# AVCF-Schematics.net
KiCad netlist of a schematic drawn in Altium Designer
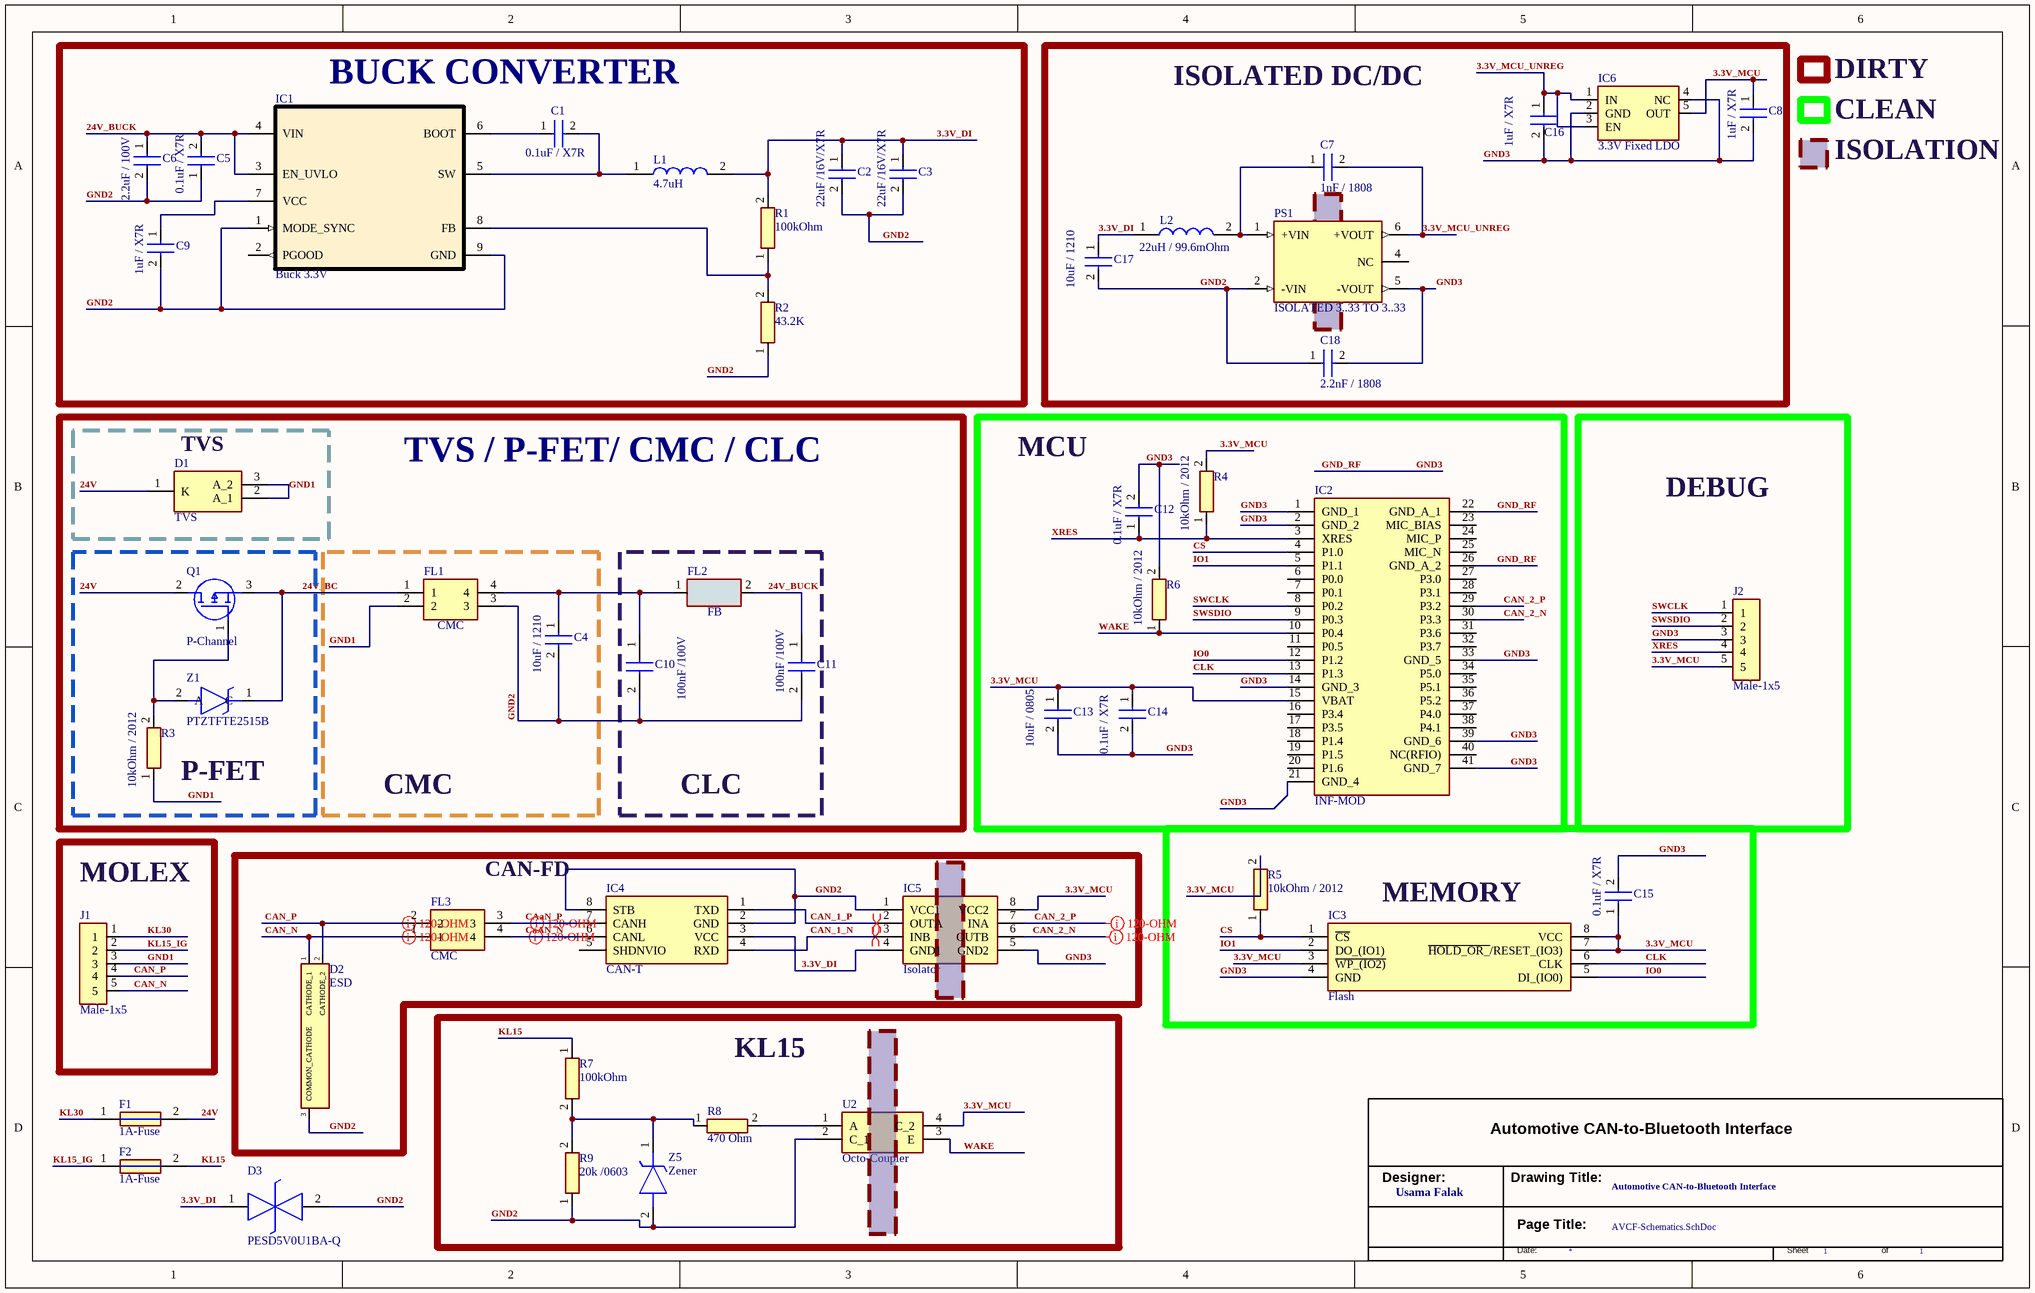
[diagram p0: AVCF-Schematics.SchDoc]

(export (version "E")
  (design (tool "Eeschema 10.0.6"))
  (components
    (comp (ref "*") (value "TitleBlock_MCPG") (libsource (lib "AVCF-SCH_Lib") (part "TitleBlock_MCPG")))
    (comp (ref "C1")
      (value "0.1uF / X7R")
      (footprint "MAJx16")
      (description "Capacitor")
      (fields (field (name "MANUFACTURER_PART_NUMBER") "MAJCU168BB7104KTEA01"))
      (libsource (lib "AVCF-SCH_Lib") (part "MAJCU168BB7104KTEA01"))
    )
    (comp (ref "C2")
      (value "22uF /16V/X7R")
      (footprint "AVCF-PCB_Lib:CAPC3225X280N")
      (description "Capacitor")
      (fields
        (field (name "MANUFACTURER_PART_NUMBER") "CGA6P1X7R1C226M250AC")
        (field (name "MOUSER PART NUMBER") "810-CGA6P1X7R1C226M")
      )
      (libsource (lib "AVCF-SCH_Lib") (part "CGA6P1X7R1C226M250AC"))
    )
    (comp (ref "C3")
      (value "22uF /16V/X7R")
      (footprint "AVCF-PCB_Lib:CAPC3225X280N")
      (description "Capacitor")
      (fields
        (field (name "MANUFACTURER_PART_NUMBER") "CGA6P1X7R1C226M250AC")
        (field (name "MOUSER PART NUMBER") "810-CGA6P1X7R1C226M")
      )
      (libsource (lib "AVCF-SCH_Lib") (part "CGA6P1X7R1C226M250AC"))
    )
    (comp (ref "C4")
      (value "10uF / 1210")
      (footprint "AVCF-PCB_Lib:CAPC3225X280N")
      (description "Capacitor")
      (fields (field (name "MANUFACTURER_PART_NUMBER") "CGA6P1X7R2A106K250AC"))
      (libsource (lib "AVCF-SCH_Lib") (part "CGA6P1X7R2A106K250AC"))
    )
    (comp (ref "C5")
      (value "0.1uF / X7R")
      (footprint "MAJx16")
      (description "Capacitor")
      (fields (field (name "MANUFACTURER_PART_NUMBER") "MAJCU168BB7104KTEA01"))
      (libsource (lib "AVCF-SCH_Lib") (part "MAJCU168BB7104KTEA01"))
    )
    (comp (ref "C6")
      (value "2.2uF / 100V")
      (footprint "AVCF-PCB_Lib:CGA4J2NP01H223J125AA")
      (description "Capacitor")
      (fields
        (field (name "MANUFACTURER_PART_NUMBER") "CGA4J1X7R2A225K125AC")
        (field (name "MOUSER PART NUMBER") "810-CGA4J7R2A225K125")
      )
      (libsource (lib "AVCF-SCH_Lib") (part "CGA4J1X7R2A225K125AC"))
    )
    (comp (ref "C7")
      (value "1nF / 1808")
      (footprint "AVCF-PCB_Lib:C1808")
      (description "Capacitor")
      (fields
        (field (name "MANUFACTURER_PART_NUMBER") "C1808C102JBGACAUTO")
        (field (name "MOUSER PART NUMBER") "80-C1808C102JBGAUTO")
      )
      (libsource (lib "AVCF-SCH_Lib") (part "C1808C102JBGACAUTO"))
    )
    (comp (ref "C8")
      (value "1uF / X7R")
      (footprint "CAPC1608X100N")
      (description "Capacitor")
      (fields
        (field (name "MANUFACTURER_PART_NUMBER") "CL10B105KB9VPNC")
        (field (name "MOUSER PART NUMBER") "187-CL10B105KB9VPNC")
      )
      (libsource (lib "AVCF-SCH_Lib") (part "CL10B105KB9VPNC"))
    )
    (comp (ref "C9")
      (value "1uF / X7R")
      (footprint "CAPC1608X100N")
      (description "Capacitor")
      (fields
        (field (name "MANUFACTURER_PART_NUMBER") "CL10B105KB9VPNC")
        (field (name "MOUSER PART NUMBER") "187-CL10B105KB9VPNC")
      )
      (libsource (lib "AVCF-SCH_Lib") (part "CL10B105KB9VPNC"))
    )
    (comp (ref "C10")
      (value "100nF /100V")
      (footprint "AVCF-PCB_Lib:CAPC1608X87N")
      (description "Multilayer Ceramic Capacitors MLCC - SMD/SMT 100V 100000pF 5% X7R 1608 AEC-Q200")
      (fields
        (field (name "MANUFACTURER_PART_NUMBER") "C0603C104J1RACAUTO7411")
        (field (name "MOUSER PART NUMBER") "80-C0603C104J1RAUTO7")
      )
      (libsource (lib "AVCF-SCH_Lib") (part "C0603C104J1RACAUTO7411"))
    )
    (comp (ref "C11")
      (value "100nF /100V")
      (footprint "AVCF-PCB_Lib:CAPC1608X87N")
      (description "Multilayer Ceramic Capacitors MLCC - SMD/SMT 100V 100000pF 5% X7R 1608 AEC-Q200")
      (fields
        (field (name "MANUFACTURER_PART_NUMBER") "C0603C104J1RACAUTO7411")
        (field (name "MOUSER PART NUMBER") "80-C0603C104J1RAUTO7")
      )
      (libsource (lib "AVCF-SCH_Lib") (part "C0603C104J1RACAUTO7411"))
    )
    (comp (ref "C12")
      (value "0.1uF / X7R")
      (footprint "MAJx16")
      (description "Capacitor")
      (fields (field (name "MANUFACTURER_PART_NUMBER") "MAJCU168BB7104KTEA01"))
      (libsource (lib "AVCF-SCH_Lib") (part "MAJCU168BB7104KTEA01"))
    )
    (comp (ref "C13")
      (value "10uF / 0805")
      (footprint "AVCF-PCB_Lib:CGA4J2NP01H223J125AA")
      (description "Capacitor")
      (fields
        (field (name "MANUFACTURER_PART_NUMBER") "CGA4J1X7S1C106M125AE")
        (field (name "MOUSER PART NUMBER") "810-CGA4J1X7S1C106MA")
      )
      (libsource (lib "AVCF-SCH_Lib") (part "CGA4J1X7S1C106M125AE"))
    )
    (comp (ref "C14")
      (value "0.1uF / X7R")
      (footprint "MAJx16")
      (description "Capacitor")
      (fields (field (name "MANUFACTURER_PART_NUMBER") "MAJCU168BB7104KTEA01"))
      (libsource (lib "AVCF-SCH_Lib") (part "MAJCU168BB7104KTEA01"))
    )
    (comp (ref "C15")
      (value "0.1uF / X7R")
      (footprint "MAJx16")
      (description "Capacitor")
      (fields (field (name "MANUFACTURER_PART_NUMBER") "MAJCU168BB7104KTEA01"))
      (libsource (lib "AVCF-SCH_Lib") (part "MAJCU168BB7104KTEA01"))
    )
    (comp (ref "C16")
      (value "1uF / X7R")
      (footprint "CAPC1608X100N")
      (description "Capacitor")
      (fields
        (field (name "MANUFACTURER_PART_NUMBER") "CL10B105KB9VPNC")
        (field (name "MOUSER PART NUMBER") "187-CL10B105KB9VPNC")
      )
      (libsource (lib "AVCF-SCH_Lib") (part "CL10B105KB9VPNC"))
    )
    (comp (ref "C17")
      (value "10uF / 1210")
      (footprint "AVCF-PCB_Lib:CAPC3225X280N")
      (description "Capacitor")
      (fields (field (name "MANUFACTURER_PART_NUMBER") "CGA6P1X7R2A106K250AC"))
      (libsource (lib "AVCF-SCH_Lib") (part "CGA6P1X7R2A106K250AC"))
    )
    (comp (ref "C18")
      (value "2.2nF / 1808")
      (footprint "AVCF-PCB_Lib:C1808")
      (description "Capacitor")
      (fields (field (name "MANUFACTURER_PART_NUMBER") "C1808C222FDGACAUTO"))
      (libsource (lib "AVCF-SCH_Lib") (part "C1808C222FDGACAUTO"))
    )
    (comp (ref "D1")
      (value "TVS")
      (footprint "AVCF-PCB_Lib:SLD8S36A")
      (description "TVS Diode (Uni-directional)")
      (fields
        (field (name "MANUFACTURER_PART_NUMBER") "SLD8S36A")
        (field (name "MOUSER PART NUMBER") "576-SLD8S36A")
      )
      (libsource (lib "AVCF-SCH_Lib") (part "SLD8S36A"))
    )
    (comp (ref "D2")
      (value "ESD")
      (footprint "SOT95P230X110-3N")
      (description "Diode ESD (Bi-directional)")
      (fields
        (field (name "MANUFACTURER_PART_NUMBER") "PESD2CAN,215")
        (field (name "MOUSER PART NUMBER") "771-PESD2CAN-T/R")
      )
      (libsource (lib "AVCF-SCH_Lib") (part "PESD2CAN,215"))
    )
    (comp (ref "D3")
      (value "PESD5V0U1BA‑Q")
      (footprint "AVCF-PCB_Lib:PESD5V0U1BA115")
      (description "Diode ESD (Bi-directional)")
      (fields
        (field (name "MANUFACTURER_PART_NUMBER") "PESD5V0U1BA-Q")
        (field (name "MOUSER PART NUMBER") "771-PESD5V0U1BA115")
      )
      (libsource (lib "AVCF-SCH_Lib") (part "PESD5V0U1BA"))
    )
    (comp (ref "F1")
      (value "1A-Fuse")
      (footprint "AVCF-PCB_Lib:FUSC6127X294N")
      (description "Fuse")
      (fields
        (field (name "MANUFACTURER_PART_NUMBER") "0451001.MRSN")
        (field (name "MOUSER PART NUMBER") "576-0451001.MRSN")
      )
      (libsource (lib "AVCF-SCH_Lib") (part "0451001.MRSN"))
    )
    (comp (ref "F2")
      (value "1A-Fuse")
      (footprint "AVCF-PCB_Lib:FUSC6127X294N")
      (description "Fuse")
      (fields
        (field (name "MANUFACTURER_PART_NUMBER") "0451001.MRSN")
        (field (name "MOUSER PART NUMBER") "576-0451001.MRSN")
      )
      (libsource (lib "AVCF-SCH_Lib") (part "0451001.MRSN"))
    )
    (comp (ref "FL1")
      (value "CMC")
      (footprint "ACT45B1012PTL003")
      (description "Filter")
      (fields
        (field (name "MANUFACTURER_PART_NUMBER") "ACT45B-510-2P-TL003")
        (field (name "MOUSER PART NUMBER") "810-ACT45B5102PTL003")
      )
      (libsource (lib "") (part "ACT45B-510-2P-TL003_1"))
    )
    (comp (ref "FL2")
      (value "FB")
      (footprint "BLM31KN102BH1L")
      (description "Filter")
      (fields
        (field (name "MANUFACTURER_PART_NUMBER") "BLM31KN601SZ1L")
        (field (name "MOUSER PART NUMBER") "81-BLM31KN601SZ1L")
      )
      (libsource (lib "AVCF-SCH_Lib") (part "BLM31KN601SZ1L"))
    )
    (comp (ref "FL3")
      (value "CMC")
      (footprint "ACT45B1012PTL003")
      (description "Filter")
      (fields
        (field (name "MANUFACTURER_PART_NUMBER") "ACT45B-510-2P-TL003")
        (field (name "MOUSER PART NUMBER") "810-ACT45B5102PTL003")
      )
      (libsource (lib "AVCF-SCH_Lib") (part "ACT45B-510-2P-TL003"))
    )
    (comp (ref "IC1")
      (value "Buck 3.3V")
      (footprint "RPE0009A")
      (fields
        (field (name "MANUFACTURER_PART_NUMBER") "LMR36506MSC3RPERQ1")
        (field (name "COPYRIGHT") "Copyright (C) 2025 Ultra Librarian. All rights reserved.")
      )
      (libsource (lib "AVCF-SCH_Lib") (part "LMR36506MSC3RPERQ1"))
    )
    (comp (ref "IC2")
      (value "INF-MOD")
      (footprint "CYW20829B0P4TAI100XUMA1")
      (description "Integrated Circuit")
      (fields
        (field (name "MANUFACTURER_PART_NUMBER") "CYW20829B0P4TAI100XUMA1")
        (field (name "MOUSER PART NUMBER") "726-CYW20829B0P4TAI1")
      )
      (libsource (lib "AVCF-SCH_Lib") (part "CYW20829B0P4TAI100XUMA1"))
    )
    (comp (ref "IC3")
      (value "Flash")
      (footprint "AVCF-PCB_Lib:SOIC127P790X216-8N")
      (description "Integrated Circuit")
      (fields
        (field (name "MANUFACTURER_PART_NUMBER") "W25Q128JVSIM")
        (field (name "MOUSER PART NUMBER") "454-W25Q128JVSIM")
      )
      (libsource (lib "AVCF-SCH_Lib") (part "W25Q128JVSIM"))
    )
    (comp (ref "IC4")
      (value "CAN-T")
      (footprint "AVCF-PCB_Lib:SOIC127P600X175-8N")
      (description "Integrated Circuit")
      (fields
        (field (name "MANUFACTURER_PART_NUMBER") "TCAN3403DRQ1")
        (field (name "MOUSER PART NUMBER") "595-TCAN3403DRQ1")
      )
      (libsource (lib "AVCF-SCH_Lib") (part "TCAN3403DRQ1"))
    )
    (comp (ref "IC5")
      (value "Isolator")
      (footprint "SOIC127P600X175-8N")
      (description "Integrated Circuit")
      (fields
        (field (name "MANUFACTURER_PART_NUMBER") "ISO7721D")
        (field (name "MOUSER PART NUMBER") "595-ISO7721D")
      )
      (libsource (lib "AVCF-SCH_Lib") (part "ISO7721D"))
    )
    (comp (ref "IC6")
      (value "3.3V Fixed LDO")
      (footprint "AVCF-PCB_Lib:SOT95P280X145-5N")
      (description "Linear Voltage Regulator IC Positive Fixed 1 Output 300mA SOT-23-5")
      (fields
        (field (name "MANUFACTURER_PART_NUMBER") "TLV70233PDBVT")
        (field (name "MOUSER PART NUMBER") "595-TLV70233PDBVT")
      )
      (libsource (lib "AVCF-SCH_Lib") (part "TLV70233PDBVT"))
    )
    (comp (ref "J1")
      (value "Male-1x5")
      (footprint "43650-05(12,13,14)")
      (description "Connector")
      (fields
        (field (name "MANUFACTURER_PART_NUMBER") "43650-0513")
        (field (name "MOUSER PART NUMBER") "538-43650-0513")
      )
      (libsource (lib "") (part "43650-0513_1"))
    )
    (comp (ref "J2")
      (value "Male-1x5")
      (footprint "43650-05(12,13,14)")
      (description "Connector")
      (fields
        (field (name "MANUFACTURER_PART_NUMBER") "43650-0513")
        (field (name "MOUSER PART NUMBER") "538-43650-0513")
      )
      (libsource (lib "AVCF-SCH_Lib") (part "43650-0513"))
    )
    (comp (ref "L1")
      (value "4.7uH")
      (footprint "AVCF-PCB_Lib:MSS6132T472MLC")
      (description "Inductor")
      (fields
        (field (name "MANUFACTURER_PART_NUMBER") "MSS6132T-472MLC")
        (field (name "MOUSER PART NUMBER") "994-MSS6132T-472MLC")
      )
      (libsource (lib "AVCF-SCH_Lib") (part "MSS6132T-472MLC"))
    )
    (comp (ref "L2")
      (value "22uH / 99.6mOhm")
      (footprint "XAL5030")
      (description "Inductor")
      (fields
        (field (name "MANUFACTURER_PART_NUMBER") "XAL5050-223MEC")
        (field (name "MOUSER PART NUMBER") "994-XAL5050-223MEC")
      )
      (libsource (lib "AVCF-SCH_Lib") (part "XAL5050-223MEC"))
    )
    (comp (ref "PS1")
      (value "ISOLATED 3..33 TO 3..33")
      (footprint "CONV_RB-3.33.3S")
      (description "1W DC/DC-Converter 'ECONOLINE' SIP7 1kV unreg")
      (fields (field (name "MF") "Recom Power") (field (name "MP") "RB-3.33.3S"))
      (libsource (lib "AVCF-SCH_Lib") (part "RB-3.33.3S"))
    )
    (comp (ref "Q1")
      (value "P-Channel")
      (footprint "FQD20N06TM")
      (description "MOSFET (P-Channel)")
      (fields
        (field (name "MANUFACTURER_PART_NUMBER") "FQD8P10TM-F085")
        (field (name "MOUSER PART NUMBER") "512-FQD8P10TM_F085")
      )
      (libsource (lib "AVCF-SCH_Lib") (part "FQD8P10TM-F085"))
    )
    (comp (ref "R1")
      (value "100kOhm")
      (footprint "AVCF-PCB_Lib:RCS0805_E3")
      (description "Resistor")
      (fields
        (field (name "MANUFACTURER_PART_NUMBER") "RCS0805100KFKEA")
        (field (name "MOUSER PART NUMBER") "71-RCS0805100KFKEA")
      )
      (libsource (lib "") (part "RCS0805100KFKEA_1"))
    )
    (comp (ref "R2")
      (value "43.2K")
      (footprint "AVCF-PCB_Lib:ERJP03_PA3_(0603)")
      (description "Resistor")
      (fields
        (field (name "MANUFACTURER_PART_NUMBER") "ERJ-PA3D4322V")
        (field (name "MOUSER PART NUMBER") "667-ERJ-PA3D4322V")
      )
      (libsource (lib "AVCF-SCH_Lib") (part "ERJ-PA3D4322V"))
    )
    (comp (ref "R3")
      (value "10kOhm / 2012")
      (footprint "RESC2012X60N")
      (description "Resistor")
      (fields
        (field (name "MANUFACTURER_PART_NUMBER") "RT0805FRE1010KL")
        (field (name "MOUSER PART NUMBER") "603-RT0805FRE1010KL")
      )
      (libsource (lib "AVCF-SCH_Lib") (part "RT0805FRE1010KL"))
    )
    (comp (ref "R4")
      (value "10kOhm / 2012")
      (footprint "RESC2012X60N")
      (description "Resistor")
      (fields
        (field (name "MANUFACTURER_PART_NUMBER") "RT0805FRE1010KL")
        (field (name "MOUSER PART NUMBER") "603-RT0805FRE1010KL")
      )
      (libsource (lib "AVCF-SCH_Lib") (part "RT0805FRE1010KL"))
    )
    (comp (ref "R5")
      (value "10kOhm / 2012")
      (footprint "RESC2012X60N")
      (description "Resistor")
      (fields
        (field (name "MANUFACTURER_PART_NUMBER") "RT0805FRE1010KL")
        (field (name "MOUSER PART NUMBER") "603-RT0805FRE1010KL")
      )
      (libsource (lib "AVCF-SCH_Lib") (part "RT0805FRE1010KL"))
    )
    (comp (ref "R6")
      (value "10kOhm / 2012")
      (footprint "RESC2012X60N")
      (description "Resistor")
      (fields
        (field (name "MANUFACTURER_PART_NUMBER") "RT0805FRE1010KL")
        (field (name "MOUSER PART NUMBER") "603-RT0805FRE1010KL")
      )
      (libsource (lib "AVCF-SCH_Lib") (part "RT0805FRE1010KL"))
    )
    (comp (ref "R7")
      (value "100kOhm")
      (footprint "AVCF-PCB_Lib:RCS0805_E3")
      (description "Resistor")
      (fields
        (field (name "MANUFACTURER_PART_NUMBER") "RCS0805100KFKEA")
        (field (name "MOUSER PART NUMBER") "71-RCS0805100KFKEA")
      )
      (libsource (lib "AVCF-SCH_Lib") (part "RCS0805100KFKEA"))
    )
    (comp (ref "R8")
      (value "470 Ohm")
      (footprint "AVCF-PCB_Lib:RESC2012X50N")
      (description "Resistor")
      (fields
        (field (name "MANUFACTURER_PART_NUMBER") "RCS0805470RJNEA")
        (field (name "MOUSER PART NUMBER") "71-RCS0805470RJNEA")
      )
      (libsource (lib "AVCF-SCH_Lib") (part "RCS0805470RJNEA"))
    )
    (comp (ref "R9")
      (value "20k /0603")
      (footprint "AVCF-PCB_Lib:RESC1608X55N")
      (description "Resistor")
      (fields
        (field (name "MANUFACTURER_PART_NUMBER") "CRCW060320K0FKEAHP")
        (field (name "MOUSER PART NUMBER") "71-CRCW060320K0FKEAH")
      )
      (libsource (lib "AVCF-SCH_Lib") (part "CRCW060320K0FKEAHP"))
    )
    (comp (ref "U2")
      (value "Octo-Coupler")
      (footprint "AVCF-PCB_Lib:SOP254P695X242-4N")
      (description "Undefined or Miscellaneous")
      (fields
        (field (name "MANUFACTURER_PART_NUMBER") "VOMA617A-3X001T")
        (field (name "MOUSER PART NUMBER") "78-VOMA617A-3X001T")
      )
      (libsource (lib "AVCF-SCH_Lib") (part "VOMA617A-3X001T"))
    )
    (comp (ref "Z1")
      (value "PTZTFTE2515B")
      (footprint "PTZTFTE2515B")
      (description "Zener Diode")
      (fields (field (name "MOUSER PART NUMBER") "755-PTZTFTE2515B"))
      (libsource (lib "AVCF-SCH_Lib") (part "PTZTFTE2515B"))
    )
    (comp (ref "Z5")
      (value "Zener")
      (footprint "AVCF-PCB_Lib:SOD3716X145N")
      (description "Zener Diode")
      (fields
        (field (name "MANUFACTURER_PART_NUMBER") "BZT52C5V1-7-F")
        (field (name "MOUSER PART NUMBER") "621-BZT52C5V1-F")
      )
      (libsource (lib "AVCF-SCH_Lib") (part "BZT52C5V1-7-F"))
    )
  )
  (nets
    (net (code "1") (name "/3.3V_DI") (class "Default")
      (node (ref "C17") (pin "1") (pinfunction "1_1") (pintype "passive"))
      (node (ref "C2") (pin "1") (pinfunction "1_1") (pintype "passive"))
      (node (ref "C3") (pin "1") (pinfunction "1_1") (pintype "passive"))
      (node (ref "D3") (pin "1") (pinfunction "K1_1") (pintype "passive"))
      (node (ref "IC4") (pin "3") (pinfunction "VCC_3") (pintype "passive"))
      (node (ref "IC5") (pin "4") (pinfunction "GND1_4") (pintype "passive"))
      (node (ref "L1") (pin "2") (pinfunction "2_2") (pintype "passive"))
      (node (ref "L2") (pin "1") (pinfunction "1_1") (pintype "passive"))
      (node (ref "R1") (pin "2") (pinfunction "2_2") (pintype "passive"))
    )
    (net (code "2") (name "/3.3V_MCU") (class "Default")
      (node (ref "C13") (pin "1") (pinfunction "1_1") (pintype "passive"))
      (node (ref "C14") (pin "1") (pinfunction "1_1") (pintype "passive"))
      (node (ref "C15") (pin "1") (pinfunction "1_1") (pintype "passive"))
      (node (ref "C8") (pin "1") (pinfunction "1_1") (pintype "passive"))
      (node (ref "IC2") (pin "15") (pinfunction "VBAT_15") (pintype "passive"))
      (node (ref "IC3") (pin "3") (pinfunction "~{WP_(IO2)}_3") (pintype "passive"))
      (node (ref "IC3") (pin "7") (pinfunction "~{HOLD_OR_}/RESET_(IO3)_7") (pintype "passive"))
      (node (ref "IC3") (pin "8") (pinfunction "VCC_8") (pintype "passive"))
      (node (ref "IC5") (pin "8") (pinfunction "VCC2_8") (pintype "passive"))
      (node (ref "IC6") (pin "5") (pinfunction "OUT_5") (pintype "passive"))
      (node (ref "J2") (pin "5") (pinfunction "5_5") (pintype "passive"))
      (node (ref "R4") (pin "2") (pinfunction "2_2") (pintype "passive"))
      (node (ref "R5") (pin "2") (pinfunction "2_2") (pintype "passive"))
      (node (ref "U2") (pin "4") (pinfunction "C_2_4") (pintype "passive"))
    )
    (net (code "3") (name "/3.3V_MCU_UNREG") (class "Default")
      (node (ref "C16") (pin "1") (pinfunction "1_1") (pintype "passive"))
      (node (ref "C7") (pin "2") (pinfunction "2_2") (pintype "passive"))
      (node (ref "IC6") (pin "1") (pinfunction "IN_1") (pintype "passive"))
      (node (ref "IC6") (pin "3") (pinfunction "EN_3") (pintype "passive"))
      (node (ref "PS1") (pin "6") (pinfunction "+VOUT_6") (pintype "output"))
    )
    (net (code "4") (name "/24V") (class "Default")
      (node (ref "D1") (pin "1") (pinfunction "K_1") (pintype "passive"))
      (node (ref "F1") (pin "2") (pinfunction "2_2") (pintype "passive"))
      (node (ref "Q1") (pin "2") (pinfunction "D_2") (pintype "passive"))
    )
    (net (code "5") (name "/24V_BC") (class "Default")
      (node (ref "FL1") (pin "1") (pinfunction "1_1") (pintype "passive"))
      (node (ref "Q1") (pin "3") (pinfunction "S_3") (pintype "passive"))
      (node (ref "Z1") (pin "1") (pinfunction "C_1") (pintype "passive"))
    )
    (net (code "6") (name "/24V_BUCK") (class "Default")
      (node (ref "C11") (pin "1") (pinfunction "1_1") (pintype "passive"))
      (node (ref "C5") (pin "2") (pinfunction "2_2") (pintype "passive"))
      (node (ref "C6") (pin "1") (pinfunction "1_1") (pintype "passive"))
      (node (ref "FL2") (pin "2") (pinfunction "2_2") (pintype "passive"))
      (node (ref "IC1") (pin "3") (pinfunction "EN_UVLO_3") (pintype "passive"))
      (node (ref "IC1") (pin "4") (pinfunction "VIN_4") (pintype "power_in"))
    )
    (net (code "7") (name "/CAN_1_N") (class "Default")
      (node (ref "IC4") (pin "4") (pinfunction "RXD_4") (pintype "passive"))
      (node (ref "IC5") (pin "3") (pinfunction "INB_3") (pintype "passive"))
    )
    (net (code "8") (name "/CAN_1_P") (class "Default")
      (node (ref "IC4") (pin "1") (pinfunction "TXD_1") (pintype "passive"))
      (node (ref "IC5") (pin "2") (pinfunction "OUTA_2") (pintype "passive"))
    )
    (net (code "9") (name "/CAN_2_N") (class "Default")
      (node (ref "IC2") (pin "30") (pinfunction "P3.3_30") (pintype "passive"))
      (node (ref "IC5") (pin "6") (pinfunction "OUTB_6") (pintype "passive"))
    )
    (net (code "10") (name "/CAN_2_P") (class "Default")
      (node (ref "IC2") (pin "29") (pinfunction "P3.2_29") (pintype "passive"))
      (node (ref "IC5") (pin "7") (pinfunction "INA_7") (pintype "passive"))
    )
    (net (code "11") (name "/CAN_N") (class "Default")
      (node (ref "D2") (pin "1") (pinfunction "CATHODE_1_1") (pintype "passive"))
      (node (ref "FL3") (pin "1") (pinfunction "1_1") (pintype "passive"))
      (node (ref "J1") (pin "5") (pinfunction "5_5") (pintype "passive"))
    )
    (net (code "12") (name "/CAN_P") (class "Default")
      (node (ref "D2") (pin "2") (pinfunction "CATHODE_2_2") (pintype "passive"))
      (node (ref "FL3") (pin "2") (pinfunction "2_2") (pintype "passive"))
      (node (ref "J1") (pin "4") (pinfunction "4_4") (pintype "passive"))
    )
    (net (code "13") (name "/CAaN_P") (class "Default")
      (node (ref "FL3") (pin "3") (pinfunction "3_3") (pintype "passive"))
      (node (ref "IC4") (pin "7") (pinfunction "CANH_7") (pintype "passive"))
    )
    (net (code "14") (name "/CLK") (class "Default")
      (node (ref "IC2") (pin "13") (pinfunction "P1.3_13") (pintype "passive"))
      (node (ref "IC3") (pin "6") (pinfunction "CLK_6") (pintype "passive"))
    )
    (net (code "15") (name "/CS") (class "Default")
      (node (ref "IC2") (pin "4") (pinfunction "P1.0_4") (pintype "passive"))
      (node (ref "IC3") (pin "1") (pinfunction "~{CS}_1") (pintype "passive"))
      (node (ref "R5") (pin "1") (pinfunction "1_1") (pintype "passive"))
    )
    (net (code "16") (name "/CaAN_N") (class "Default")
      (node (ref "FL3") (pin "4") (pinfunction "4_4") (pintype "passive"))
      (node (ref "IC4") (pin "6") (pinfunction "CANL_6") (pintype "passive"))
    )
    (net (code "17") (name "/GND1") (class "Default")
      (node (ref "D1") (pin "2") (pinfunction "A_1_2") (pintype "passive"))
      (node (ref "D1") (pin "3") (pinfunction "A_2_3") (pintype "passive"))
      (node (ref "FL1") (pin "2") (pinfunction "2_2") (pintype "passive"))
      (node (ref "J1") (pin "3") (pinfunction "3_3") (pintype "passive"))
      (node (ref "R3") (pin "1") (pinfunction "1_1") (pintype "passive"))
    )
    (net (code "18") (name "/GND2") (class "Default")
      (node (ref "C10") (pin "2") (pinfunction "2_2") (pintype "passive"))
      (node (ref "C11") (pin "2") (pinfunction "2_2") (pintype "passive"))
      (node (ref "C17") (pin "2") (pinfunction "2_2") (pintype "passive"))
      (node (ref "C18") (pin "1") (pinfunction "1_1") (pintype "passive"))
      (node (ref "C2") (pin "2") (pinfunction "2_2") (pintype "passive"))
      (node (ref "C3") (pin "2") (pinfunction "2_2") (pintype "passive"))
      (node (ref "C4") (pin "2") (pinfunction "2_2") (pintype "passive"))
      (node (ref "C5") (pin "1") (pinfunction "1_1") (pintype "passive"))
      (node (ref "C6") (pin "2") (pinfunction "2_2") (pintype "passive"))
      (node (ref "C9") (pin "2") (pinfunction "2_2") (pintype "passive"))
      (node (ref "D2") (pin "3") (pinfunction "COMMON_CATHODE_3") (pintype "passive"))
      (node (ref "D3") (pin "2") (pinfunction "K2_2") (pintype "passive"))
      (node (ref "FL1") (pin "3") (pinfunction "3_3") (pintype "passive"))
      (node (ref "IC1") (pin "1") (pinfunction "MODE_SYNC_1") (pintype "input"))
      (node (ref "IC1") (pin "9") (pinfunction "GND_9") (pintype "power_in"))
      (node (ref "IC4") (pin "2") (pinfunction "GND_2") (pintype "passive"))
      (node (ref "IC4") (pin "8") (pinfunction "STB_8") (pintype "passive"))
      (node (ref "IC5") (pin "1") (pinfunction "VCC1_1") (pintype "passive"))
      (node (ref "PS1") (pin "2") (pinfunction "-VIN_2") (pintype "input"))
      (node (ref "R2") (pin "1") (pinfunction "1_1") (pintype "passive"))
      (node (ref "R9") (pin "1") (pinfunction "1_1") (pintype "passive"))
      (node (ref "U2") (pin "2") (pinfunction "C_1_2") (pintype "passive"))
      (node (ref "Z5") (pin "2") (pinfunction "A_2") (pintype "passive"))
    )
    (net (code "19") (name "/GND3") (class "Default")
      (node (ref "C12") (pin "2") (pinfunction "2_2") (pintype "passive"))
      (node (ref "C13") (pin "2") (pinfunction "2_2") (pintype "passive"))
      (node (ref "C14") (pin "2") (pinfunction "2_2") (pintype "passive"))
      (node (ref "C15") (pin "2") (pinfunction "2_2") (pintype "passive"))
      (node (ref "C16") (pin "2") (pinfunction "2_2") (pintype "passive"))
      (node (ref "C18") (pin "2") (pinfunction "2_2") (pintype "passive"))
      (node (ref "C8") (pin "2") (pinfunction "2_2") (pintype "passive"))
      (node (ref "IC2") (pin "1") (pinfunction "GND_1_1") (pintype "passive"))
      (node (ref "IC2") (pin "14") (pinfunction "GND_3_14") (pintype "passive"))
      (node (ref "IC2") (pin "2") (pinfunction "GND_2_2") (pintype "passive"))
      (node (ref "IC2") (pin "21") (pinfunction "GND_4_21") (pintype "passive"))
      (node (ref "IC2") (pin "22") (pinfunction "GND_A_1_22") (pintype "passive"))
      (node (ref "IC2") (pin "26") (pinfunction "GND_A_2_26") (pintype "passive"))
      (node (ref "IC2") (pin "33") (pinfunction "GND_5_33") (pintype "passive"))
      (node (ref "IC2") (pin "39") (pinfunction "GND_6_39") (pintype "passive"))
      (node (ref "IC2") (pin "41") (pinfunction "GND_7_41") (pintype "passive"))
      (node (ref "IC3") (pin "4") (pinfunction "GND_4") (pintype "passive"))
      (node (ref "IC5") (pin "5") (pinfunction "GND2_5") (pintype "passive"))
      (node (ref "IC6") (pin "2") (pinfunction "GND_2") (pintype "passive"))
      (node (ref "IC6") (pin "4") (pinfunction "NC_4") (pintype "passive"))
      (node (ref "J2") (pin "3") (pinfunction "3_3") (pintype "passive"))
      (node (ref "PS1") (pin "5") (pinfunction "-VOUT_5") (pintype "output"))
      (node (ref "R6") (pin "2") (pinfunction "2_2") (pintype "passive"))
    )
    (net (code "20") (name "/IO0") (class "Default")
      (node (ref "IC2") (pin "12") (pinfunction "P1.2_12") (pintype "passive"))
      (node (ref "IC3") (pin "5") (pinfunction "DI_(IO0)_5") (pintype "passive"))
    )
    (net (code "21") (name "/IO1") (class "Default")
      (node (ref "IC2") (pin "5") (pinfunction "P1.1_5") (pintype "passive"))
      (node (ref "IC3") (pin "2") (pinfunction "DO_(IO1)_2") (pintype "passive"))
    )
    (net (code "22") (name "/KL15") (class "Default")
      (node (ref "F2") (pin "2") (pinfunction "2_2") (pintype "passive"))
      (node (ref "R7") (pin "1") (pinfunction "1_1") (pintype "passive"))
    )
    (net (code "23") (name "/KL15_IG") (class "Default")
      (node (ref "F2") (pin "1") (pinfunction "1_1") (pintype "passive"))
      (node (ref "J1") (pin "2") (pinfunction "2_2") (pintype "passive"))
    )
    (net (code "24") (name "/KL30") (class "Default")
      (node (ref "F1") (pin "1") (pinfunction "1_1") (pintype "passive"))
      (node (ref "J1") (pin "1") (pinfunction "1_1") (pintype "passive"))
    )
    (net (code "25") (name "/SWCLK") (class "Default")
      (node (ref "IC2") (pin "8") (pinfunction "P0.2_8") (pintype "passive"))
      (node (ref "J2") (pin "1") (pinfunction "1_1") (pintype "passive"))
    )
    (net (code "26") (name "/SWSDIO") (class "Default")
      (node (ref "IC2") (pin "9") (pinfunction "P0.3_9") (pintype "passive"))
      (node (ref "J2") (pin "2") (pinfunction "2_2") (pintype "passive"))
    )
    (net (code "27") (name "/WAKE") (class "Default")
      (node (ref "IC2") (pin "10") (pinfunction "P0.4_10") (pintype "passive"))
      (node (ref "R6") (pin "1") (pinfunction "1_1") (pintype "passive"))
      (node (ref "U2") (pin "3") (pinfunction "E_3") (pintype "passive"))
    )
    (net (code "28") (name "/XRES") (class "Default")
      (node (ref "C12") (pin "1") (pinfunction "1_1") (pintype "passive"))
      (node (ref "IC2") (pin "3") (pinfunction "XRES_3") (pintype "passive"))
      (node (ref "J2") (pin "4") (pinfunction "4_4") (pintype "passive"))
      (node (ref "R4") (pin "1") (pinfunction "1_1") (pintype "passive"))
    )
    (net (code "29") (name "Net-(C10-Pad1)") (class "Default")
      (node (ref "C10") (pin "1") (pinfunction "1_1") (pintype "passive"))
      (node (ref "C4") (pin "1") (pinfunction "1_1") (pintype "passive"))
      (node (ref "FL1") (pin "4") (pinfunction "4_4") (pintype "passive"))
      (node (ref "FL2") (pin "1") (pinfunction "1_1") (pintype "passive"))
    )
    (net (code "30") (name "Net-(IC1-BOOT)") (class "Default")
      (node (ref "C1") (pin "1") (pinfunction "1_1") (pintype "passive"))
      (node (ref "IC1") (pin "6") (pinfunction "BOOT_6") (pintype "passive"))
    )
    (net (code "31") (name "Net-(IC1-FB)") (class "Default")
      (node (ref "IC1") (pin "8") (pinfunction "FB_8") (pintype "passive"))
      (node (ref "R1") (pin "1") (pinfunction "1_1") (pintype "passive"))
      (node (ref "R2") (pin "2") (pinfunction "2_2") (pintype "passive"))
    )
    (net (code "32") (name "Net-(IC1-SW)") (class "Default")
      (node (ref "C1") (pin "2") (pinfunction "2_2") (pintype "passive"))
      (node (ref "IC1") (pin "5") (pinfunction "SW_5") (pintype "power_in"))
      (node (ref "L1") (pin "1") (pinfunction "1_1") (pintype "passive"))
    )
    (net (code "33") (name "Net-(IC1-VCC)") (class "Default")
      (node (ref "C9") (pin "1") (pinfunction "1_1") (pintype "passive"))
      (node (ref "IC1") (pin "7") (pinfunction "VCC_7") (pintype "power_in"))
    )
    (net (code "34") (name "Net-(PS1-+VIN)") (class "Default")
      (node (ref "C7") (pin "1") (pinfunction "1_1") (pintype "passive"))
      (node (ref "L2") (pin "2") (pinfunction "2_2") (pintype "passive"))
      (node (ref "PS1") (pin "1") (pinfunction "+VIN_1") (pintype "input"))
    )
    (net (code "35") (name "Net-(Q1-G)") (class "Default")
      (node (ref "Q1") (pin "1") (pinfunction "G_1") (pintype "passive"))
      (node (ref "R3") (pin "2") (pinfunction "2_2") (pintype "passive"))
      (node (ref "Z1") (pin "2") (pinfunction "A_2") (pintype "passive"))
    )
    (net (code "36") (name "Net-(U2-A)") (class "Default")
      (node (ref "R8") (pin "2") (pinfunction "2_2") (pintype "passive"))
      (node (ref "U2") (pin "1") (pinfunction "A_1") (pintype "passive"))
    )
    (net (code "37") (name "Net-(Z5-K)") (class "Default")
      (node (ref "R7") (pin "2") (pinfunction "2_2") (pintype "passive"))
      (node (ref "R8") (pin "1") (pinfunction "1_1") (pintype "passive"))
      (node (ref "R9") (pin "2") (pinfunction "2_2") (pintype "passive"))
      (node (ref "Z5") (pin "1") (pinfunction "K_1") (pintype "passive"))
    )
    (net (code "38") (name "unconnected-(IC1-PGOOD-Pad2)") (class "Default")
      (node (ref "IC1") (pin "2") (pinfunction "PGOOD_2") (pintype "output"))
    )
    (net (code "39") (name "unconnected-(IC2-MIC_BIAS-Pad23)") (class "Default")
      (node (ref "IC2") (pin "23") (pinfunction "MIC_BIAS_23") (pintype "passive"))
    )
    (net (code "40") (name "unconnected-(IC2-MIC_N-Pad25)") (class "Default")
      (node (ref "IC2") (pin "25") (pinfunction "MIC_N_25") (pintype "passive"))
    )
    (net (code "41") (name "unconnected-(IC2-MIC_P-Pad24)") (class "Default")
      (node (ref "IC2") (pin "24") (pinfunction "MIC_P_24") (pintype "passive"))
    )
    (net (code "42") (name "unconnected-(IC2-NC(RFIO)-Pad40)") (class "Default")
      (node (ref "IC2") (pin "40") (pinfunction "NC(RFIO)_40") (pintype "passive"))
    )
    (net (code "43") (name "unconnected-(IC2-P0.0-Pad6)") (class "Default")
      (node (ref "IC2") (pin "6") (pinfunction "P0.0_6") (pintype "passive"))
    )
    (net (code "44") (name "unconnected-(IC2-P0.1-Pad7)") (class "Default")
      (node (ref "IC2") (pin "7") (pinfunction "P0.1_7") (pintype "passive"))
    )
    (net (code "45") (name "unconnected-(IC2-P0.5-Pad11)") (class "Default")
      (node (ref "IC2") (pin "11") (pinfunction "P0.5_11") (pintype "passive"))
    )
    (net (code "46") (name "unconnected-(IC2-P1.4-Pad18)") (class "Default")
      (node (ref "IC2") (pin "18") (pinfunction "P1.4_18") (pintype "passive"))
    )
    (net (code "47") (name "unconnected-(IC2-P1.5-Pad19)") (class "Default")
      (node (ref "IC2") (pin "19") (pinfunction "P1.5_19") (pintype "passive"))
    )
    (net (code "48") (name "unconnected-(IC2-P1.6-Pad20)") (class "Default")
      (node (ref "IC2") (pin "20") (pinfunction "P1.6_20") (pintype "passive"))
    )
    (net (code "49") (name "unconnected-(IC2-P3.0-Pad27)") (class "Default")
      (node (ref "IC2") (pin "27") (pinfunction "P3.0_27") (pintype "passive"))
    )
    (net (code "50") (name "unconnected-(IC2-P3.1-Pad28)") (class "Default")
      (node (ref "IC2") (pin "28") (pinfunction "P3.1_28") (pintype "passive"))
    )
    (net (code "51") (name "unconnected-(IC2-P3.4-Pad16)") (class "Default")
      (node (ref "IC2") (pin "16") (pinfunction "P3.4_16") (pintype "passive"))
    )
    (net (code "52") (name "unconnected-(IC2-P3.5-Pad17)") (class "Default")
      (node (ref "IC2") (pin "17") (pinfunction "P3.5_17") (pintype "passive"))
    )
    (net (code "53") (name "unconnected-(IC2-P3.6-Pad31)") (class "Default")
      (node (ref "IC2") (pin "31") (pinfunction "P3.6_31") (pintype "passive"))
    )
    (net (code "54") (name "unconnected-(IC2-P3.7-Pad32)") (class "Default")
      (node (ref "IC2") (pin "32") (pinfunction "P3.7_32") (pintype "passive"))
    )
    (net (code "55") (name "unconnected-(IC2-P4.0-Pad37)") (class "Default")
      (node (ref "IC2") (pin "37") (pinfunction "P4.0_37") (pintype "passive"))
    )
    (net (code "56") (name "unconnected-(IC2-P4.1-Pad38)") (class "Default")
      (node (ref "IC2") (pin "38") (pinfunction "P4.1_38") (pintype "passive"))
    )
    (net (code "57") (name "unconnected-(IC2-P5.0-Pad34)") (class "Default")
      (node (ref "IC2") (pin "34") (pinfunction "P5.0_34") (pintype "passive"))
    )
    (net (code "58") (name "unconnected-(IC2-P5.1-Pad35)") (class "Default")
      (node (ref "IC2") (pin "35") (pinfunction "P5.1_35") (pintype "passive"))
    )
    (net (code "59") (name "unconnected-(IC2-P5.2-Pad36)") (class "Default")
      (node (ref "IC2") (pin "36") (pinfunction "P5.2_36") (pintype "passive"))
    )
    (net (code "60") (name "unconnected-(IC4-SHDNVIO-Pad5)") (class "Default")
      (node (ref "IC4") (pin "5") (pinfunction "SHDNVIO_5") (pintype "passive"))
    )
    (net (code "61") (name "unconnected-(PS1-NC-Pad4)") (class "Default")
      (node (ref "PS1") (pin "4") (pinfunction "NC_4") (pintype "passive"))
    )
  )
)
